# design.net
KiCad netlist of a schematic drawn in Altium Designer
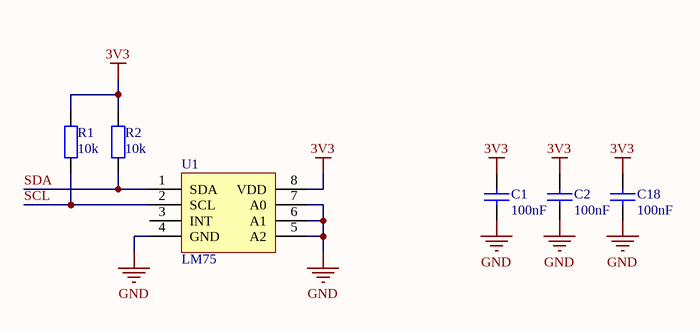
[diagram p0: 传感器.SchDoc]

(export (version "E")
  (design (tool "Eeschema 10.0.6"))
  (components
    (comp (ref "C1")
      (value "100nF")
      (footprint "0805")
      (description "Capacitor")
      (fields (field (name "PUBLISHER") "Altium Limited"))
      (libsource (lib "yitiandelan") (part "Cap"))
    )
    (comp (ref "C2")
      (value "100nF")
      (footprint "0805")
      (description "Capacitor")
      (fields (field (name "PUBLISHER") "Altium Limited"))
      (libsource (lib "yitiandelan") (part "Cap"))
    )
    (comp (ref "C18")
      (value "100nF")
      (footprint "0805")
      (description "Capacitor")
      (fields (field (name "PUBLISHER") "Altium Limited"))
      (libsource (lib "yitiandelan") (part "Cap"))
    )
    (comp (ref "R1")
      (value "10k")
      (footprint "0805")
      (description "Resistor")
      (fields (field (name "PUBLISHER") "Altium Limited"))
      (libsource (lib "yitiandelan") (part "Res2"))
    )
    (comp (ref "R2")
      (value "10k")
      (footprint "0805")
      (description "Resistor")
      (fields (field (name "PUBLISHER") "Altium Limited"))
      (libsource (lib "yitiandelan") (part "Res2"))
    )
    (comp (ref "U1") (value "LM75") (footprint "SO8_N") (libsource (lib "yitiandelan") (part "LM75")))
  )
  (nets
    (net (code "1") (name "/SCL") (class "Default")
      (node (ref "R1") (pin "2") (pinfunction "2_2") (pintype "passive"))
      (node (ref "U1") (pin "2") (pinfunction "SCL_2") (pintype "passive"))
    )
    (net (code "2") (name "/SDA") (class "Default")
      (node (ref "R2") (pin "2") (pinfunction "2_2") (pintype "passive"))
      (node (ref "U1") (pin "1") (pinfunction "SDA_1") (pintype "passive"))
    )
    (net (code "3") (name "3V3") (class "Default")
      (node (ref "C1") (pin "2") (pinfunction "2_2") (pintype "passive"))
      (node (ref "C18") (pin "2") (pinfunction "2_2") (pintype "passive"))
      (node (ref "C2") (pin "2") (pinfunction "2_2") (pintype "passive"))
      (node (ref "R1") (pin "1") (pinfunction "1_1") (pintype "passive"))
      (node (ref "R2") (pin "1") (pinfunction "1_1") (pintype "passive"))
      (node (ref "U1") (pin "8") (pinfunction "VDD_8") (pintype "passive"))
    )
    (net (code "4") (name "GND") (class "Default")
      (node (ref "C1") (pin "1") (pinfunction "1_1") (pintype "passive"))
      (node (ref "C18") (pin "1") (pinfunction "1_1") (pintype "passive"))
      (node (ref "C2") (pin "1") (pinfunction "1_1") (pintype "passive"))
      (node (ref "U1") (pin "4") (pinfunction "GND_4") (pintype "passive"))
      (node (ref "U1") (pin "5") (pinfunction "A2_5") (pintype "passive"))
      (node (ref "U1") (pin "6") (pinfunction "A1_6") (pintype "passive"))
      (node (ref "U1") (pin "7") (pinfunction "A0_7") (pintype "passive"))
    )
    (net (code "5") (name "unconnected-(U1-INT-Pad3)") (class "Default")
      (node (ref "U1") (pin "3") (pinfunction "INT_3") (pintype "passive"))
    )
  )
)
